# fpga_block.net
KiCad netlist of a schematic drawn in Altium Designer
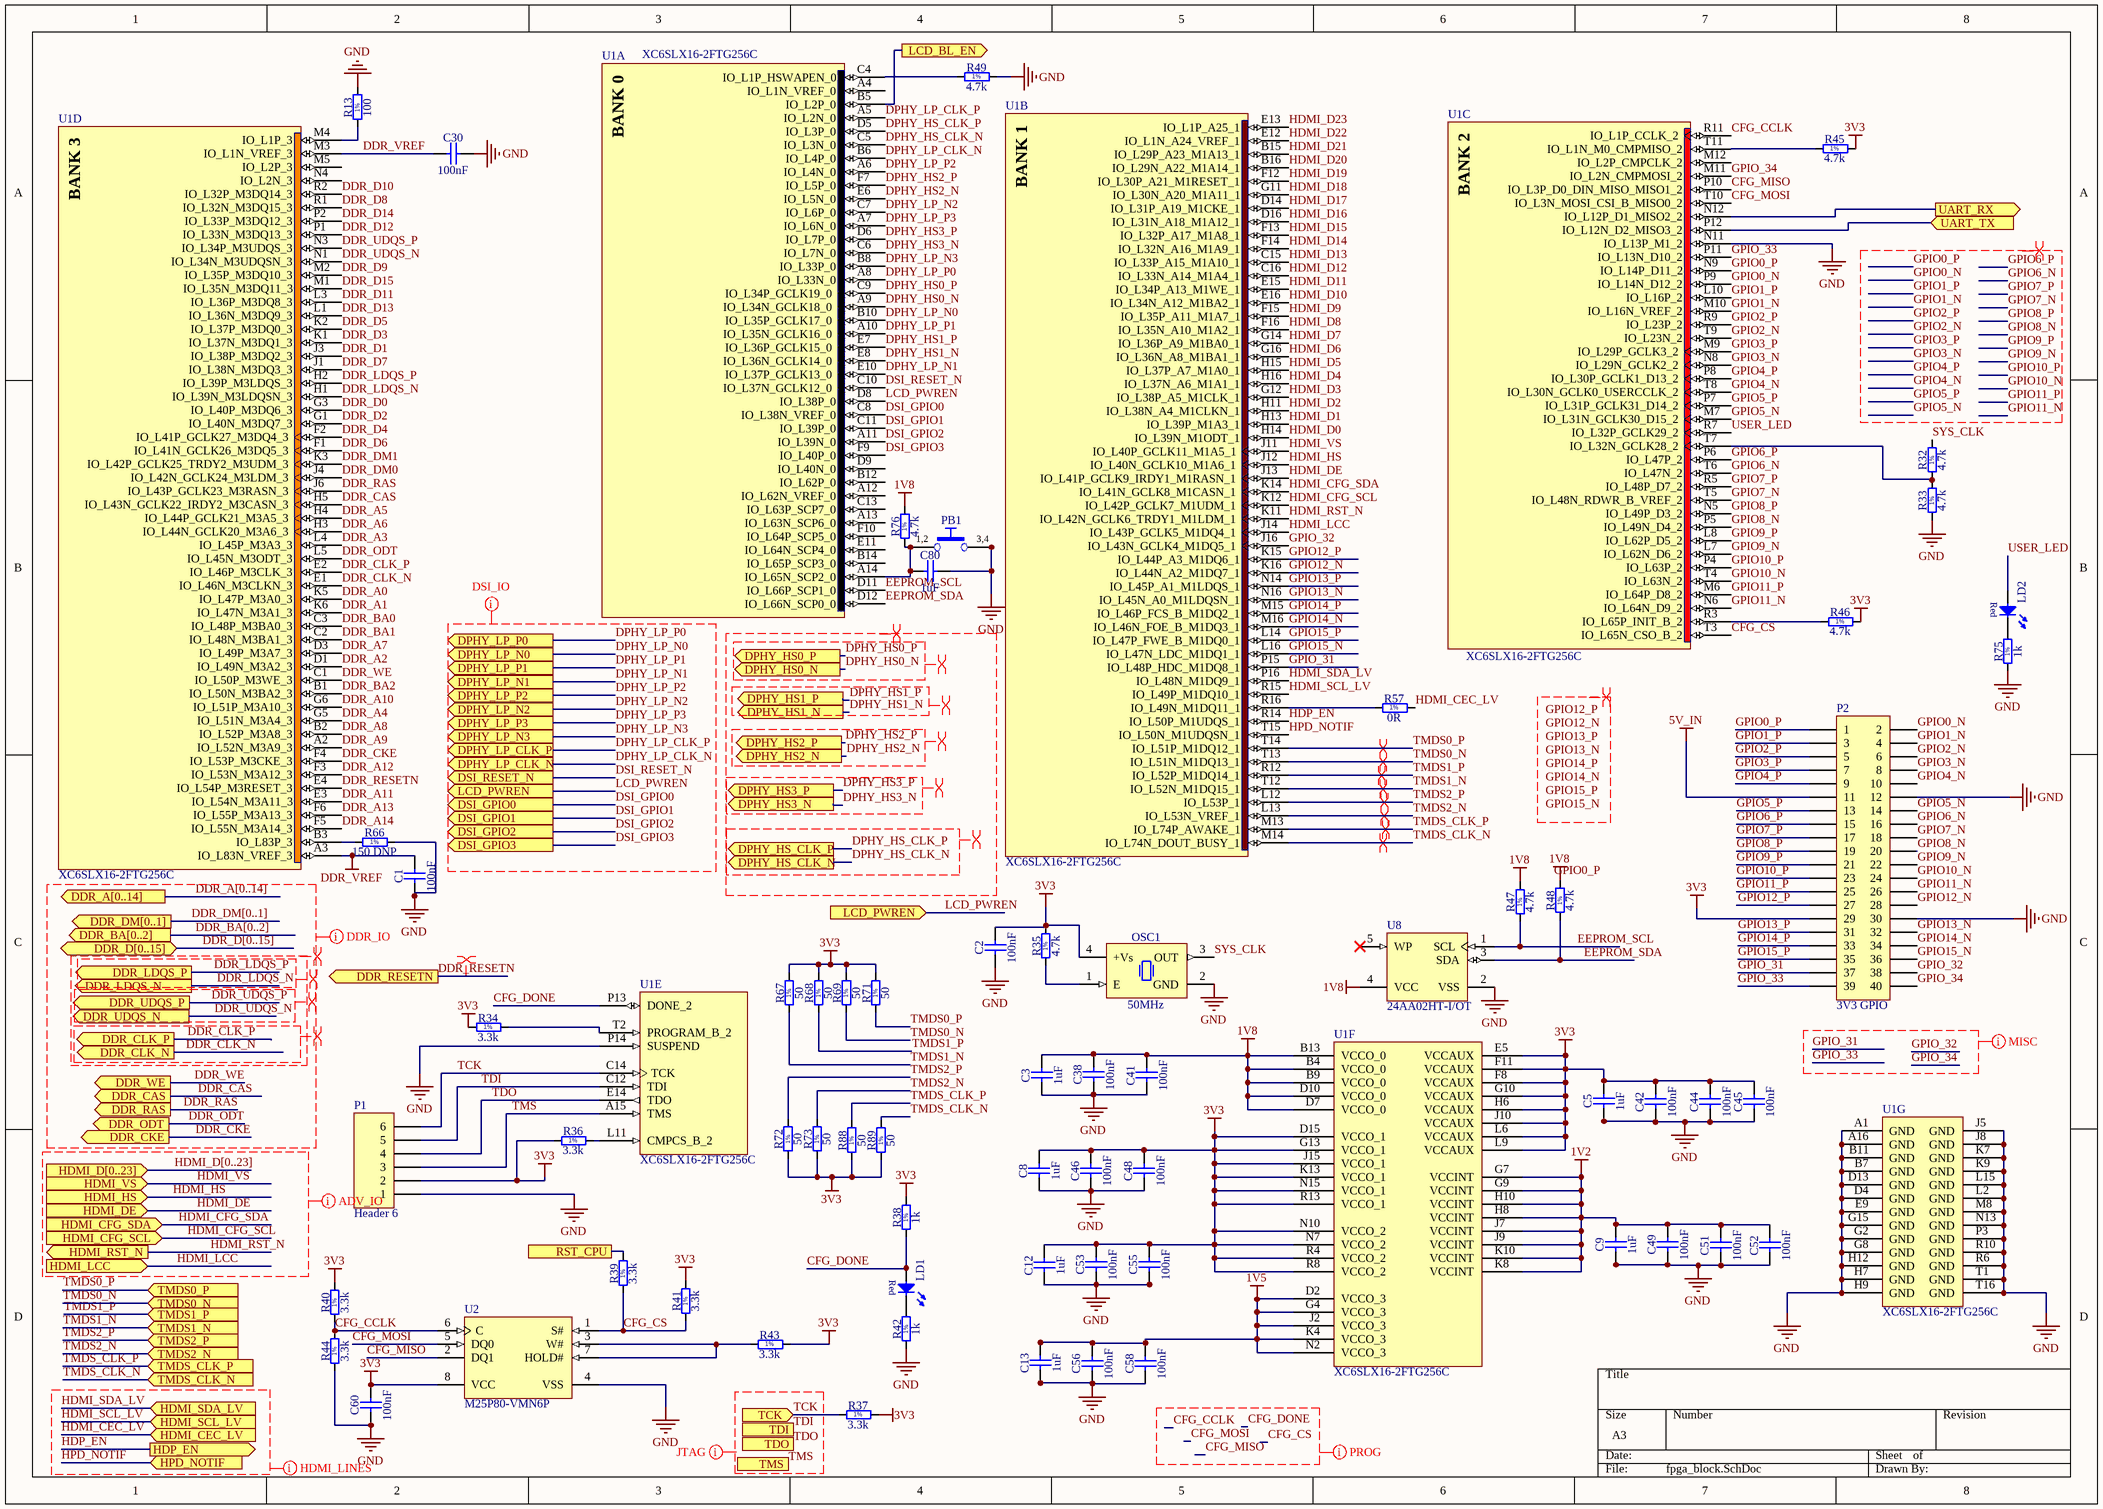
[diagram p0: fpga_block.SchDoc]

(export (version "E")
  (design (tool "Eeschema 10.0.6"))
  (components
    (comp (ref "C1")
      (value "100nF")
      (footprint "CAPC1005X55N")
      (description "Non-polarised capacitor")
      (fields
        (field (name "PART NUMBER") "CC0402_100NF_16V_10%_X5R")
        (field (name "VOLTAGE") "16V")
        (field (name "AUTHOR") "CERN DEM JLC")
      )
      (libsource (lib "Capacitors") (part "Capacitor - non polarized"))
    )
    (comp (ref "C2")
      (value "100nF")
      (footprint "CAPC1005X55N")
      (description "Non-polarised capacitor")
      (fields
        (field (name "PART NUMBER") "CC0402_100NF_16V_10%_X5R")
        (field (name "VOLTAGE") "16V")
        (field (name "AUTHOR") "CERN DEM JLC")
      )
      (libsource (lib "Capacitors") (part "Capacitor - non polarized"))
    )
    (comp (ref "C3")
      (value "1uF")
      (footprint "CAPC1005X55N")
      (description "Non-polarised capacitor")
      (fields
        (field (name "PART NUMBER") "CC0402_100NF_16V_10%_X5R")
        (field (name "VOLTAGE") "16V")
        (field (name "AUTHOR") "CERN DEM JLC")
      )
      (libsource (lib "Capacitors") (part "Capacitor - non polarized"))
    )
    (comp (ref "C5")
      (value "1uF")
      (footprint "CAPC1005X55N")
      (description "Non-polarised capacitor")
      (fields
        (field (name "PART NUMBER") "CC0402_100NF_16V_10%_X5R")
        (field (name "VOLTAGE") "16V")
        (field (name "AUTHOR") "CERN DEM JLC")
      )
      (libsource (lib "Capacitors") (part "Capacitor - non polarized"))
    )
    (comp (ref "C8")
      (value "1uF")
      (footprint "CAPC1005X55N")
      (description "Non-polarised capacitor")
      (fields
        (field (name "PART NUMBER") "CC0402_100NF_16V_10%_X5R")
        (field (name "VOLTAGE") "16V")
        (field (name "AUTHOR") "CERN DEM JLC")
      )
      (libsource (lib "Capacitors") (part "Capacitor - non polarized"))
    )
    (comp (ref "C9")
      (value "1uF")
      (footprint "CAPC1005X55N")
      (description "Non-polarised capacitor")
      (fields
        (field (name "PART NUMBER") "CC0402_100NF_16V_10%_X5R")
        (field (name "VOLTAGE") "16V")
        (field (name "AUTHOR") "CERN DEM JLC")
      )
      (libsource (lib "Capacitors") (part "Capacitor - non polarized"))
    )
    (comp (ref "C12")
      (value "1uF")
      (footprint "CAPC1005X55N")
      (description "Non-polarised capacitor")
      (fields
        (field (name "PART NUMBER") "CC0402_100NF_16V_10%_X5R")
        (field (name "VOLTAGE") "16V")
        (field (name "AUTHOR") "CERN DEM JLC")
      )
      (libsource (lib "Capacitors") (part "Capacitor - non polarized"))
    )
    (comp (ref "C13")
      (value "1uF")
      (footprint "CAPC1005X55N")
      (description "Non-polarised capacitor")
      (fields
        (field (name "PART NUMBER") "CC0402_100NF_16V_10%_X5R")
        (field (name "VOLTAGE") "16V")
        (field (name "AUTHOR") "CERN DEM JLC")
      )
      (libsource (lib "Capacitors") (part "Capacitor - non polarized"))
    )
    (comp (ref "C30")
      (value "100nF")
      (footprint "CAPC1005X55N")
      (description "Non-polarised capacitor")
      (fields
        (field (name "PART NUMBER") "CC0402_100NF_16V_10%_X5R")
        (field (name "VOLTAGE") "16V")
        (field (name "AUTHOR") "CERN DEM JLC")
      )
      (libsource (lib "Capacitors") (part "Capacitor - non polarized"))
    )
    (comp (ref "C38")
      (value "100nF")
      (footprint "CAPC1005X55N")
      (description "Non-polarised capacitor")
      (fields
        (field (name "PART NUMBER") "CC0402_100NF_16V_10%_X5R")
        (field (name "VOLTAGE") "16V")
        (field (name "AUTHOR") "CERN DEM JLC")
      )
      (libsource (lib "Capacitors") (part "Capacitor - non polarized"))
    )
    (comp (ref "C41")
      (value "100nF")
      (footprint "CAPC1005X55N")
      (description "Non-polarised capacitor")
      (fields
        (field (name "PART NUMBER") "CC0402_100NF_16V_10%_X5R")
        (field (name "VOLTAGE") "16V")
        (field (name "AUTHOR") "CERN DEM JLC")
      )
      (libsource (lib "Capacitors") (part "Capacitor - non polarized"))
    )
    (comp (ref "C42")
      (value "100nF")
      (footprint "CAPC1005X55N")
      (description "Non-polarised capacitor")
      (fields
        (field (name "PART NUMBER") "CC0402_100NF_16V_10%_X5R")
        (field (name "VOLTAGE") "16V")
        (field (name "AUTHOR") "CERN DEM JLC")
      )
      (libsource (lib "Capacitors") (part "Capacitor - non polarized"))
    )
    (comp (ref "C44")
      (value "100nF")
      (footprint "CAPC1005X55N")
      (description "Non-polarised capacitor")
      (fields
        (field (name "PART NUMBER") "CC0402_100NF_16V_10%_X5R")
        (field (name "VOLTAGE") "16V")
        (field (name "AUTHOR") "CERN DEM JLC")
      )
      (libsource (lib "Capacitors") (part "Capacitor - non polarized"))
    )
    (comp (ref "C45")
      (value "100nF")
      (footprint "CAPC1005X55N")
      (description "Non-polarised capacitor")
      (fields
        (field (name "PART NUMBER") "CC0402_100NF_16V_10%_X5R")
        (field (name "VOLTAGE") "16V")
        (field (name "AUTHOR") "CERN DEM JLC")
      )
      (libsource (lib "Capacitors") (part "Capacitor - non polarized"))
    )
    (comp (ref "C46")
      (value "100nF")
      (footprint "CAPC1005X55N")
      (description "Non-polarised capacitor")
      (fields
        (field (name "PART NUMBER") "CC0402_100NF_16V_10%_X5R")
        (field (name "VOLTAGE") "16V")
        (field (name "AUTHOR") "CERN DEM JLC")
      )
      (libsource (lib "Capacitors") (part "Capacitor - non polarized"))
    )
    (comp (ref "C48")
      (value "100nF")
      (footprint "CAPC1005X55N")
      (description "Non-polarised capacitor")
      (fields
        (field (name "PART NUMBER") "CC0402_100NF_16V_10%_X5R")
        (field (name "VOLTAGE") "16V")
        (field (name "AUTHOR") "CERN DEM JLC")
      )
      (libsource (lib "Capacitors") (part "Capacitor - non polarized"))
    )
    (comp (ref "C49")
      (value "100nF")
      (footprint "CAPC1005X55N")
      (description "Non-polarised capacitor")
      (fields
        (field (name "PART NUMBER") "CC0402_100NF_16V_10%_X5R")
        (field (name "VOLTAGE") "16V")
        (field (name "AUTHOR") "CERN DEM JLC")
      )
      (libsource (lib "Capacitors") (part "Capacitor - non polarized"))
    )
    (comp (ref "C51")
      (value "100nF")
      (footprint "CAPC1005X55N")
      (description "Non-polarised capacitor")
      (fields
        (field (name "PART NUMBER") "CC0402_100NF_16V_10%_X5R")
        (field (name "VOLTAGE") "16V")
        (field (name "AUTHOR") "CERN DEM JLC")
      )
      (libsource (lib "Capacitors") (part "Capacitor - non polarized"))
    )
    (comp (ref "C52")
      (value "100nF")
      (footprint "CAPC1005X55N")
      (description "Non-polarised capacitor")
      (fields
        (field (name "PART NUMBER") "CC0402_100NF_16V_10%_X5R")
        (field (name "VOLTAGE") "16V")
        (field (name "AUTHOR") "CERN DEM JLC")
      )
      (libsource (lib "Capacitors") (part "Capacitor - non polarized"))
    )
    (comp (ref "C53")
      (value "100nF")
      (footprint "CAPC1005X55N")
      (description "Non-polarised capacitor")
      (fields
        (field (name "PART NUMBER") "CC0402_100NF_16V_10%_X5R")
        (field (name "VOLTAGE") "16V")
        (field (name "AUTHOR") "CERN DEM JLC")
      )
      (libsource (lib "Capacitors") (part "Capacitor - non polarized"))
    )
    (comp (ref "C55")
      (value "100nF")
      (footprint "CAPC1005X55N")
      (description "Non-polarised capacitor")
      (fields
        (field (name "PART NUMBER") "CC0402_100NF_16V_10%_X5R")
        (field (name "VOLTAGE") "16V")
        (field (name "AUTHOR") "CERN DEM JLC")
      )
      (libsource (lib "Capacitors") (part "Capacitor - non polarized"))
    )
    (comp (ref "C56")
      (value "100nF")
      (footprint "CAPC1005X55N")
      (description "Non-polarised capacitor")
      (fields
        (field (name "PART NUMBER") "CC0402_100NF_16V_10%_X5R")
        (field (name "VOLTAGE") "16V")
        (field (name "AUTHOR") "CERN DEM JLC")
      )
      (libsource (lib "Capacitors") (part "Capacitor - non polarized"))
    )
    (comp (ref "C58")
      (value "100nF")
      (footprint "CAPC1005X55N")
      (description "Non-polarised capacitor")
      (fields
        (field (name "PART NUMBER") "CC0402_100NF_16V_10%_X5R")
        (field (name "VOLTAGE") "16V")
        (field (name "AUTHOR") "CERN DEM JLC")
      )
      (libsource (lib "Capacitors") (part "Capacitor - non polarized"))
    )
    (comp (ref "C60")
      (value "100nF")
      (footprint "CAPC2013X100N")
      (description "Non-polarised capacitor")
      (fields
        (field (name "PART NUMBER") "CC0805_1.5NF_50V_5%_C0G")
        (field (name "VOLTAGE") "50V")
        (field (name "AUTHOR") "CERN DEM BC")
      )
      (libsource (lib "Capacitors") (part "Capacitor - non polarized"))
    )
    (comp (ref "C80")
      (value "1uF")
      (footprint "CAPC1005X55N")
      (description "Non-polarised capacitor")
      (fields
        (field (name "PART NUMBER") "CC0402_100NF_16V_10%_X5R")
        (field (name "VOLTAGE") "16V")
        (field (name "AUTHOR") "CERN DEM JLC")
      )
      (libsource (lib "Capacitors") (part "Capacitor - non polarized"))
    )
    (comp (ref "LD1")
      (value "Super Red")
      (footprint "LED_OSRAM_LSR976")
      (description "LED Red 1C 2A")
      (fields
        (field (name "PART NUMBER") "LED_OSRAM_LSR976")
        (field (name "MANUFACTURER") "OSRAM")
        (field (name "AUTHOR") "CERN DEM JLC")
      )
      (libsource (lib "ICs And Semiconductors") (part "LED Red 1C 2A"))
    )
    (comp (ref "LD2")
      (value "Super Red")
      (footprint "LED_OSRAM_LSR976")
      (description "LED Red 1C 2A")
      (fields
        (field (name "PART NUMBER") "LED_OSRAM_LSR976")
        (field (name "MANUFACTURER") "OSRAM")
        (field (name "AUTHOR") "CERN DEM JLC")
      )
      (libsource (lib "ICs And Semiconductors") (part "LED Red 1C 2A"))
    )
    (comp (ref "OSC1")
      (value "50MHz")
      (footprint "OSC_IQD_CFPS-69")
      (description "Oscillator 4 pins 1=E 2=GND 3=OUT 4=+Vs")
      (fields
        (field (name "PART NUMBER") "OSC_50MHZ_IQD_LFSPXO009592")
        (field (name "MANUFACTURER") "IQD FREQUENCY PRODUCTS")
        (field (name "AUTHOR") "CERN DEM JLC")
      )
      (libsource (lib "ICs And Semiconductors") (part "Oscillator 1E 2GND 3OUT 4Vs"))
    )
    (comp (ref "P1")
      (value "Header 6")
      (footprint "HDR1X6")
      (description "Header, 6-Pin")
      (fields (field (name "PUBLISHER") "Altium Limited"))
      (libsource (lib "Miscellaneous Connectors") (part "Header 6"))
    )
    (comp (ref "P2")
      (value "3V3 GPIO")
      (footprint "HDR2X20")
      (description "Header, 20-Pin, Dual row")
      (fields (field (name "PUBLISHER") "Altium Limited"))
      (libsource (lib "Miscellaneous Connectors") (part "Header 20X2"))
    )
    (comp (ref "PB1")
      (value "Push Button")
      (footprint "PB_TYCO_FSM6JSMA")
      (description "Push-Button Switch SPDT")
      (fields
        (field (name "PART NUMBER") "PB_TYCO_FSM6JSMA")
        (field (name "MANUFACTURER") "TYCO ELECTRONICS")
        (field (name "AUTHOR") "CERN DEM JLC")
      )
      (libsource (lib "Eletro-mechanical") (part "PB SPST 12NO-34NO"))
    )
    (comp (ref "R13")
      (value "100")
      (footprint "RESC1608X55N")
      (description "Resistor - 1%")
      (fields
        (field (name "PART NUMBER") "R0603_100K_1%_0.1W_100PPM")
        (field (name "POWER") "0.1W")
        (field (name "AUTHOR") "CERN DEM JLC")
      )
      (libsource (lib "Resistors") (part "Resistor - 1%"))
    )
    (comp (ref "R32")
      (value "4.7k")
      (footprint "RESC1608X55N")
      (description "Resistor - 1%")
      (fields
        (field (name "PART NUMBER") "R0603_100K_1%_0.1W_100PPM")
        (field (name "POWER") "0.1W")
        (field (name "AUTHOR") "CERN DEM JLC")
      )
      (libsource (lib "Resistors") (part "Resistor - 1%"))
    )
    (comp (ref "R33")
      (value "4.7k")
      (footprint "RESC1608X55N")
      (description "Resistor - 1%")
      (fields
        (field (name "PART NUMBER") "R0603_100K_1%_0.1W_100PPM")
        (field (name "POWER") "0.1W")
        (field (name "AUTHOR") "CERN DEM JLC")
      )
      (libsource (lib "Resistors") (part "Resistor - 1%"))
    )
    (comp (ref "R34")
      (value "3.3k")
      (footprint "RESC1608X55N")
      (description "Resistor - 1%")
      (fields
        (field (name "PART NUMBER") "R0603_100K_1%_0.1W_100PPM")
        (field (name "POWER") "0.1W")
        (field (name "AUTHOR") "CERN DEM JLC")
      )
      (libsource (lib "Resistors") (part "Resistor - 1%"))
    )
    (comp (ref "R35")
      (value "4.7k")
      (footprint "RESC1608X55N")
      (description "Resistor - 1%")
      (fields
        (field (name "PART NUMBER") "R0603_100K_1%_0.1W_100PPM")
        (field (name "POWER") "0.1W")
        (field (name "AUTHOR") "CERN DEM JLC")
      )
      (libsource (lib "Resistors") (part "Resistor - 1%"))
    )
    (comp (ref "R36")
      (value "3.3k")
      (footprint "RESC1608X55N")
      (description "Resistor - 1%")
      (fields
        (field (name "PART NUMBER") "R0603_100K_1%_0.1W_100PPM")
        (field (name "POWER") "0.1W")
        (field (name "AUTHOR") "CERN DEM JLC")
      )
      (libsource (lib "Resistors") (part "Resistor - 1%"))
    )
    (comp (ref "R37")
      (value "3.3k")
      (footprint "RESC1608X55N")
      (description "Resistor - 1%")
      (fields
        (field (name "PART NUMBER") "R0603_100K_1%_0.1W_100PPM")
        (field (name "POWER") "0.1W")
        (field (name "AUTHOR") "CERN DEM JLC")
      )
      (libsource (lib "Resistors") (part "Resistor - 1%"))
    )
    (comp (ref "R38")
      (value "1k")
      (footprint "RESC1608X55N")
      (description "Resistor - 1%")
      (fields
        (field (name "PART NUMBER") "R0603_100K_1%_0.1W_100PPM")
        (field (name "POWER") "0.1W")
        (field (name "AUTHOR") "CERN DEM JLC")
      )
      (libsource (lib "Resistors") (part "Resistor - 1%"))
    )
    (comp (ref "R39")
      (value "3.3k")
      (footprint "RESC1608X55N")
      (description "Resistor - 1%")
      (fields
        (field (name "PART NUMBER") "R0603_100K_1%_0.1W_100PPM")
        (field (name "POWER") "0.1W")
        (field (name "AUTHOR") "CERN DEM JLC")
      )
      (libsource (lib "Resistors") (part "Resistor - 1%"))
    )
    (comp (ref "R40")
      (value "3.3k")
      (footprint "RESC1608X55N")
      (description "Resistor - 1%")
      (fields
        (field (name "PART NUMBER") "R0603_100K_1%_0.1W_100PPM")
        (field (name "POWER") "0.1W")
        (field (name "AUTHOR") "CERN DEM JLC")
      )
      (libsource (lib "Resistors") (part "Resistor - 1%"))
    )
    (comp (ref "R41")
      (value "3.3k")
      (footprint "RESC1608X55N")
      (description "Resistor - 1%")
      (fields
        (field (name "PART NUMBER") "R0603_100K_1%_0.1W_100PPM")
        (field (name "POWER") "0.1W")
        (field (name "AUTHOR") "CERN DEM JLC")
      )
      (libsource (lib "Resistors") (part "Resistor - 1%"))
    )
    (comp (ref "R42")
      (value "1k")
      (footprint "RESC1608X55N")
      (description "Resistor - 1%")
      (fields
        (field (name "PART NUMBER") "R0603_100K_1%_0.1W_100PPM")
        (field (name "POWER") "0.1W")
        (field (name "AUTHOR") "CERN DEM JLC")
      )
      (libsource (lib "Resistors") (part "Resistor - 1%"))
    )
    (comp (ref "R43")
      (value "3.3k")
      (footprint "RESC1608X55N")
      (description "Resistor - 1%")
      (fields
        (field (name "PART NUMBER") "R0603_100K_1%_0.1W_100PPM")
        (field (name "POWER") "0.1W")
        (field (name "AUTHOR") "CERN DEM JLC")
      )
      (libsource (lib "Resistors") (part "Resistor - 1%"))
    )
    (comp (ref "R44")
      (value "3.3k")
      (footprint "RESC1608X55N")
      (description "Resistor - 1%")
      (fields
        (field (name "PART NUMBER") "R0603_100K_1%_0.1W_100PPM")
        (field (name "POWER") "0.1W")
        (field (name "AUTHOR") "CERN DEM JLC")
      )
      (libsource (lib "Resistors") (part "Resistor - 1%"))
    )
    (comp (ref "R45")
      (value "4.7k")
      (footprint "RESC1608X55N")
      (description "Resistor - 1%")
      (fields
        (field (name "PART NUMBER") "R0603_100K_1%_0.1W_100PPM")
        (field (name "POWER") "0.1W")
        (field (name "AUTHOR") "CERN DEM JLC")
      )
      (libsource (lib "Resistors") (part "Resistor - 1%"))
    )
    (comp (ref "R46")
      (value "4.7k")
      (footprint "RESC1608X55N")
      (description "Resistor - 1%")
      (fields
        (field (name "PART NUMBER") "R0603_100K_1%_0.1W_100PPM")
        (field (name "POWER") "0.1W")
        (field (name "AUTHOR") "CERN DEM JLC")
      )
      (libsource (lib "Resistors") (part "Resistor - 1%"))
    )
    (comp (ref "R47")
      (value "4.7k")
      (footprint "RESC1608X55N")
      (description "Resistor - 1%")
      (fields
        (field (name "PART NUMBER") "R0603_100K_1%_0.1W_100PPM")
        (field (name "POWER") "0.1W")
        (field (name "AUTHOR") "CERN DEM JLC")
      )
      (libsource (lib "Resistors") (part "Resistor - 1%"))
    )
    (comp (ref "R48")
      (value "4.7k")
      (footprint "RESC1608X55N")
      (description "Resistor - 1%")
      (fields
        (field (name "PART NUMBER") "R0603_100K_1%_0.1W_100PPM")
        (field (name "POWER") "0.1W")
        (field (name "AUTHOR") "CERN DEM JLC")
      )
      (libsource (lib "Resistors") (part "Resistor - 1%"))
    )
    (comp (ref "R49")
      (value "4.7k")
      (footprint "RESC1608X55N")
      (description "Resistor - 1%")
      (fields
        (field (name "PART NUMBER") "R0603_100K_1%_0.1W_100PPM")
        (field (name "POWER") "0.1W")
        (field (name "AUTHOR") "CERN DEM JLC")
      )
      (libsource (lib "Resistors") (part "Resistor - 1%"))
    )
    (comp (ref "R57")
      (value "0R")
      (footprint "RESC1608X55N")
      (description "Resistor - 1%")
      (fields
        (field (name "PART NUMBER") "R0603_100K_1%_0.1W_100PPM")
        (field (name "POWER") "0.1W")
        (field (name "AUTHOR") "CERN DEM JLC")
      )
      (libsource (lib "Resistors") (part "Resistor - 1%"))
    )
    (comp (ref "R66")
      (value "150 DNP")
      (footprint "RESC1608X55N")
      (description "Resistor - 1%")
      (fields
        (field (name "PART NUMBER") "R0603_100K_1%_0.1W_100PPM")
        (field (name "POWER") "0.1W")
        (field (name "AUTHOR") "CERN DEM JLC")
      )
      (libsource (lib "Resistors") (part "Resistor - 1%"))
    )
    (comp (ref "R67")
      (value "50")
      (footprint "RESC1005X40N")
      (description "Resistor - 1%")
      (fields
        (field (name "PART NUMBER") "R0402_51K_1%_0.0625W_100PPM")
        (field (name "POWER") "0.0625W")
        (field (name "AUTHOR") "CERN DEM JLC")
      )
      (libsource (lib "Resistors") (part "Resistor - 1%"))
    )
    (comp (ref "R68")
      (value "50")
      (footprint "RESC1005X40N")
      (description "Resistor - 1%")
      (fields
        (field (name "PART NUMBER") "R0402_51K_1%_0.0625W_100PPM")
        (field (name "POWER") "0.0625W")
        (field (name "AUTHOR") "CERN DEM JLC")
      )
      (libsource (lib "Resistors") (part "Resistor - 1%"))
    )
    (comp (ref "R69")
      (value "50")
      (footprint "RESC1005X40N")
      (description "Resistor - 1%")
      (fields
        (field (name "PART NUMBER") "R0402_51K_1%_0.0625W_100PPM")
        (field (name "POWER") "0.0625W")
        (field (name "AUTHOR") "CERN DEM JLC")
      )
      (libsource (lib "Resistors") (part "Resistor - 1%"))
    )
    (comp (ref "R71")
      (value "50")
      (footprint "RESC1005X40N")
      (description "Resistor - 1%")
      (fields
        (field (name "PART NUMBER") "R0402_51K_1%_0.0625W_100PPM")
        (field (name "POWER") "0.0625W")
        (field (name "AUTHOR") "CERN DEM JLC")
      )
      (libsource (lib "Resistors") (part "Resistor - 1%"))
    )
    (comp (ref "R72")
      (value "50")
      (footprint "RESC1005X40N")
      (description "Resistor - 1%")
      (fields
        (field (name "PART NUMBER") "R0402_51K_1%_0.0625W_100PPM")
        (field (name "POWER") "0.0625W")
        (field (name "AUTHOR") "CERN DEM JLC")
      )
      (libsource (lib "Resistors") (part "Resistor - 1%"))
    )
    (comp (ref "R73")
      (value "50")
      (footprint "RESC1005X40N")
      (description "Resistor - 1%")
      (fields
        (field (name "PART NUMBER") "R0402_51K_1%_0.0625W_100PPM")
        (field (name "POWER") "0.0625W")
        (field (name "AUTHOR") "CERN DEM JLC")
      )
      (libsource (lib "Resistors") (part "Resistor - 1%"))
    )
    (comp (ref "R75")
      (value "1k")
      (footprint "RESC1608X55N")
      (description "Resistor - 1%")
      (fields
        (field (name "PART NUMBER") "R0603_100K_1%_0.1W_100PPM")
        (field (name "POWER") "0.1W")
        (field (name "AUTHOR") "CERN DEM JLC")
      )
      (libsource (lib "Resistors") (part "Resistor - 1%"))
    )
    (comp (ref "R76")
      (value "4.7k")
      (footprint "RESC1608X55N")
      (description "Resistor - 1%")
      (fields
        (field (name "PART NUMBER") "R0603_100K_1%_0.1W_100PPM")
        (field (name "POWER") "0.1W")
        (field (name "AUTHOR") "CERN DEM JLC")
      )
      (libsource (lib "Resistors") (part "Resistor - 1%"))
    )
    (comp (ref "R88")
      (value "50")
      (footprint "RESC1005X40N")
      (description "Resistor - 1%")
      (fields
        (field (name "PART NUMBER") "R0402_51K_1%_0.0625W_100PPM")
        (field (name "POWER") "0.0625W")
        (field (name "AUTHOR") "CERN DEM JLC")
      )
      (libsource (lib "Resistors") (part "Resistor - 1%"))
    )
    (comp (ref "R89")
      (value "50")
      (footprint "RESC1005X40N")
      (description "Resistor - 1%")
      (fields
        (field (name "PART NUMBER") "R0402_51K_1%_0.0625W_100PPM")
        (field (name "POWER") "0.0625W")
        (field (name "AUTHOR") "CERN DEM JLC")
      )
      (libsource (lib "Resistors") (part "Resistor - 1%"))
    )
    (comp (ref "U1")
      (value "XC6SLX16-2FTG256C")
      (footprint "FTG256")
      (libsource (lib "Xilinx Spartan-6") (part "XC6SLX16-2FTG256C"))
    )
    (comp (ref "U2")
      (value "M25P80-VMN6P")
      (footprint "MICT-MN-8_N")
      (description "8 Mb (x1) Serial NOR Flash Memory, 75 MHz, 2.7 to 3.6 V, 8-pin SO8 Narrow (MN), Tube")
      (fields (field (name "VOLTAGE") "2.7V-3.6V") (field (name "MANUFACTURER") "Micron"))
      (libsource (lib "Micron Memory Serial NOR Flash") (part "M25P80-VMN6P"))
    )
    (comp (ref "U8")
      (value "24AA02HT-I/OT")
      (footprint "SOT-23-OT5_L")
      (description "2Kbit, 400kHz, 1.7V, I2C Serial EEPROM, 5-Pin SOT-23, Industrial Temperature, Tape and Reel")
      (fields (field (name "MANUFACTURER") "Microchip"))
      (libsource (lib "Microchip I2C Serial EEPROM") (part "24AA02HT-I/OT"))
    )
  )
  (nets
    (net (code "1") (name "/CFG_CCLK") (class "Default")
      (node (ref "R40") (pin "1") (pinfunction "1_1") (pintype "passive"))
      (node (ref "R44") (pin "2") (pinfunction "2_2") (pintype "passive"))
      (node (ref "U1") (pin "R11") (pinfunction "IO_L1P_CCLK_2_R11") (pintype "bidirectional"))
      (node (ref "U2") (pin "6") (pinfunction "C_6") (pintype "input"))
    )
    (net (code "2") (name "/CFG_CS") (class "Default")
      (node (ref "R39") (pin "1") (pinfunction "1_1") (pintype "passive"))
      (node (ref "R41") (pin "1") (pinfunction "1_1") (pintype "passive"))
      (node (ref "U1") (pin "T3") (pinfunction "IO_L65N_CSO_B_2_T3") (pintype "bidirectional"))
      (node (ref "U2") (pin "1") (pinfunction "S#_1") (pintype "input"))
    )
    (net (code "3") (name "/CFG_DONE") (class "Default")
      (node (ref "LD1") (pin "2") (pinfunction "A_2") (pintype "passive"))
      (node (ref "R38") (pin "1") (pinfunction "1_1") (pintype "passive"))
      (node (ref "U1") (pin "P13") (pinfunction "DONE_2_P13") (pintype "bidirectional"))
    )
    (net (code "4") (name "/CFG_MISO") (class "Default")
      (node (ref "U1") (pin "P10") (pinfunction "IO_L3P_D0_DIN_MISO_MISO1_2_P10") (pintype "bidirectional"))
      (node (ref "U2") (pin "2") (pinfunction "DQ1_2") (pintype "tri_state"))
    )
    (net (code "5") (name "/CFG_MOSI") (class "Default")
      (node (ref "U1") (pin "T10") (pinfunction "IO_L3N_MOSI_CSI_B_MISO0_2_T10") (pintype "bidirectional"))
      (node (ref "U2") (pin "5") (pinfunction "DQ0_5") (pintype "input"))
    )
    (net (code "6") (name "/DDR_A0") (class "Default")
      (node (ref "U1") (pin "K5") (pinfunction "IO_L47P_M3A0_3_K5") (pintype "bidirectional"))
    )
    (net (code "7") (name "/DDR_A1") (class "Default")
      (node (ref "U1") (pin "K6") (pinfunction "IO_L47N_M3A1_3_K6") (pintype "bidirectional"))
    )
    (net (code "8") (name "/DDR_A2") (class "Default")
      (node (ref "U1") (pin "D1") (pinfunction "IO_L49N_M3A2_3_D1") (pintype "bidirectional"))
    )
    (net (code "9") (name "/DDR_A3") (class "Default")
      (node (ref "U1") (pin "L4") (pinfunction "IO_L45P_M3A3_3_L4") (pintype "bidirectional"))
    )
    (net (code "10") (name "/DDR_A4") (class "Default")
      (node (ref "U1") (pin "G5") (pinfunction "IO_L51N_M3A4_3_G5") (pintype "bidirectional"))
    )
    (net (code "11") (name "/DDR_A5") (class "Default")
      (node (ref "U1") (pin "H4") (pinfunction "IO_L44P_GCLK21_M3A5_3_H4") (pintype "bidirectional"))
    )
    (net (code "12") (name "/DDR_A6") (class "Default")
      (node (ref "U1") (pin "H3") (pinfunction "IO_L44N_GCLK20_M3A6_3_H3") (pintype "bidirectional"))
    )
    (net (code "13") (name "/DDR_A7") (class "Default")
      (node (ref "U1") (pin "D3") (pinfunction "IO_L49P_M3A7_3_D3") (pintype "bidirectional"))
    )
    (net (code "14") (name "/DDR_A8") (class "Default")
      (node (ref "U1") (pin "B2") (pinfunction "IO_L52P_M3A8_3_B2") (pintype "bidirectional"))
    )
    (net (code "15") (name "/DDR_A9") (class "Default")
      (node (ref "U1") (pin "A2") (pinfunction "IO_L52N_M3A9_3_A2") (pintype "bidirectional"))
    )
    (net (code "16") (name "/DDR_A10") (class "Default")
      (node (ref "U1") (pin "G6") (pinfunction "IO_L51P_M3A10_3_G6") (pintype "bidirectional"))
    )
    (net (code "17") (name "/DDR_A11") (class "Default")
      (node (ref "U1") (pin "E3") (pinfunction "IO_L54N_M3A11_3_E3") (pintype "bidirectional"))
    )
    (net (code "18") (name "/DDR_A12") (class "Default")
      (node (ref "U1") (pin "F3") (pinfunction "IO_L53N_M3A12_3_F3") (pintype "bidirectional"))
    )
    (net (code "19") (name "/DDR_A13") (class "Default")
      (node (ref "U1") (pin "F6") (pinfunction "IO_L55P_M3A13_3_F6") (pintype "bidirectional"))
    )
    (net (code "20") (name "/DDR_A14") (class "Default")
      (node (ref "U1") (pin "F5") (pinfunction "IO_L55N_M3A14_3_F5") (pintype "bidirectional"))
    )
    (net (code "22") (name "/DDR_BA0") (class "Default")
      (node (ref "U1") (pin "C3") (pinfunction "IO_L48P_M3BA0_3_C3") (pintype "bidirectional"))
    )
    (net (code "23") (name "/DDR_BA1") (class "Default")
      (node (ref "U1") (pin "C2") (pinfunction "IO_L48N_M3BA1_3_C2") (pintype "bidirectional"))
    )
    (net (code "24") (name "/DDR_BA2") (class "Default")
      (node (ref "U1") (pin "B1") (pinfunction "IO_L50N_M3BA2_3_B1") (pintype "bidirectional"))
    )
    (net (code "26") (name "/DDR_CAS") (class "Default")
      (node (ref "U1") (pin "H5") (pinfunction "IO_L43N_GCLK22_IRDY2_M3CASN_3_H5") (pintype "bidirectional"))
    )
    (net (code "27") (name "/DDR_CKE") (class "Default")
      (node (ref "U1") (pin "F4") (pinfunction "IO_L53P_M3CKE_3_F4") (pintype "bidirectional"))
    )
    (net (code "28") (name "/DDR_CLK_N") (class "Default")
      (node (ref "U1") (pin "E1") (pinfunction "IO_L46N_M3CLKN_3_E1") (pintype "bidirectional"))
    )
    (net (code "29") (name "/DDR_CLK_P") (class "Default")
      (node (ref "U1") (pin "E2") (pinfunction "IO_L46P_M3CLK_3_E2") (pintype "bidirectional"))
    )
    (net (code "30") (name "/DDR_D0") (class "Default")
      (node (ref "U1") (pin "G3") (pinfunction "IO_L40P_M3DQ6_3_G3") (pintype "bidirectional"))
    )
    (net (code "31") (name "/DDR_D1") (class "Default")
      (node (ref "U1") (pin "J3") (pinfunction "IO_L38P_M3DQ2_3_J3") (pintype "bidirectional"))
    )
    (net (code "32") (name "/DDR_D2") (class "Default")
      (node (ref "U1") (pin "G1") (pinfunction "IO_L40N_M3DQ7_3_G1") (pintype "bidirectional"))
    )
    (net (code "33") (name "/DDR_D3") (class "Default")
      (node (ref "U1") (pin "K1") (pinfunction "IO_L37N_M3DQ1_3_K1") (pintype "bidirectional"))
    )
    (net (code "34") (name "/DDR_D4") (class "Default")
      (node (ref "U1") (pin "F2") (pinfunction "IO_L41P_GCLK27_M3DQ4_3_F2") (pintype "bidirectional"))
    )
    (net (code "35") (name "/DDR_D5") (class "Default")
      (node (ref "U1") (pin "K2") (pinfunction "IO_L37P_M3DQ0_3_K2") (pintype "bidirectional"))
    )
    (net (code "36") (name "/DDR_D6") (class "Default")
      (node (ref "U1") (pin "F1") (pinfunction "IO_L41N_GCLK26_M3DQ5_3_F1") (pintype "bidirectional"))
    )
    (net (code "37") (name "/DDR_D7") (class "Default")
      (node (ref "U1") (pin "J1") (pinfunction "IO_L38N_M3DQ3_3_J1") (pintype "bidirectional"))
    )
    (net (code "38") (name "/DDR_D8") (class "Default")
      (node (ref "U1") (pin "R1") (pinfunction "IO_L32N_M3DQ15_3_R1") (pintype "bidirectional"))
    )
    (net (code "39") (name "/DDR_D9") (class "Default")
      (node (ref "U1") (pin "M2") (pinfunction "IO_L35P_M3DQ10_3_M2") (pintype "bidirectional"))
    )
    (net (code "40") (name "/DDR_D10") (class "Default")
      (node (ref "U1") (pin "R2") (pinfunction "IO_L32P_M3DQ14_3_R2") (pintype "bidirectional"))
    )
    (net (code "41") (name "/DDR_D11") (class "Default")
      (node (ref "U1") (pin "L3") (pinfunction "IO_L36P_M3DQ8_3_L3") (pintype "bidirectional"))
    )
    (net (code "42") (name "/DDR_D12") (class "Default")
      (node (ref "U1") (pin "P1") (pinfunction "IO_L33N_M3DQ13_3_P1") (pintype "bidirectional"))
    )
    (net (code "43") (name "/DDR_D13") (class "Default")
      (node (ref "U1") (pin "L1") (pinfunction "IO_L36N_M3DQ9_3_L1") (pintype "bidirectional"))
    )
    (net (code "44") (name "/DDR_D14") (class "Default")
      (node (ref "U1") (pin "P2") (pinfunction "IO_L33P_M3DQ12_3_P2") (pintype "bidirectional"))
    )
    (net (code "45") (name "/DDR_D15") (class "Default")
      (node (ref "U1") (pin "M1") (pinfunction "IO_L35N_M3DQ11_3_M1") (pintype "bidirectional"))
    )
    (net (code "46") (name "/DDR_DM0") (class "Default")
      (node (ref "U1") (pin "J4") (pinfunction "IO_L42N_GCLK24_M3LDM_3_J4") (pintype "bidirectional"))
    )
    (net (code "47") (name "/DDR_DM1") (class "Default")
      (node (ref "U1") (pin "K3") (pinfunction "IO_L42P_GCLK25_TRDY2_M3UDM_3_K3") (pintype "bidirectional"))
    )
    (net (code "50") (name "/DDR_LDQS_N") (class "Default")
      (node (ref "U1") (pin "H1") (pinfunction "IO_L39N_M3LDQSN_3_H1") (pintype "bidirectional"))
    )
    (net (code "51") (name "/DDR_LDQS_P") (class "Default")
      (node (ref "U1") (pin "H2") (pinfunction "IO_L39P_M3LDQS_3_H2") (pintype "bidirectional"))
    )
    (net (code "52") (name "/DDR_ODT") (class "Default")
      (node (ref "U1") (pin "L5") (pinfunction "IO_L45N_M3ODT_3_L5") (pintype "bidirectional"))
    )
    (net (code "53") (name "/DDR_RAS") (class "Default")
      (node (ref "U1") (pin "J6") (pinfunction "IO_L43P_GCLK23_M3RASN_3_J6") (pintype "bidirectional"))
    )
    (net (code "54") (name "/DDR_RESETN") (class "Default")
      (node (ref "U1") (pin "E4") (pinfunction "IO_L54P_M3RESET_3_E4") (pintype "bidirectional"))
    )
    (net (code "55") (name "/DDR_UDQS_N") (class "Default")
      (node (ref "U1") (pin "N1") (pinfunction "IO_L34N_M3UDQSN_3_N1") (pintype "bidirectional"))
    )
    (net (code "56") (name "/DDR_UDQS_P") (class "Default")
      (node (ref "U1") (pin "N3") (pinfunction "IO_L34P_M3UDQS_3_N3") (pintype "bidirectional"))
    )
    (net (code "57") (name "/DDR_WE") (class "Default")
      (node (ref "U1") (pin "C1") (pinfunction "IO_L50P_M3WE_3_C1") (pintype "bidirectional"))
    )
    (net (code "58") (name "/DPHY_HS0_N") (class "Default")
      (node (ref "U1") (pin "A9") (pinfunction "IO_L34N_GCLK18_0_A9") (pintype "bidirectional"))
    )
    (net (code "59") (name "/DPHY_HS0_P") (class "Default")
      (node (ref "U1") (pin "C9") (pinfunction "IO_L34P_GCLK19_0_C9") (pintype "bidirectional"))
    )
    (net (code "60") (name "/DPHY_HS1_N") (class "Default")
      (node (ref "U1") (pin "E8") (pinfunction "IO_L36N_GCLK14_0_E8") (pintype "bidirectional"))
    )
    (net (code "61") (name "/DPHY_HS1_P") (class "Default")
      (node (ref "U1") (pin "E7") (pinfunction "IO_L36P_GCLK15_0_E7") (pintype "bidirectional"))
    )
    (net (code "62") (name "/DPHY_HS2_N") (class "Default")
      (node (ref "U1") (pin "E6") (pinfunction "IO_L5N_0_E6") (pintype "bidirectional"))
    )
    (net (code "63") (name "/DPHY_HS2_P") (class "Default")
      (node (ref "U1") (pin "F7") (pinfunction "IO_L5P_0_F7") (pintype "bidirectional"))
    )
    (net (code "64") (name "/DPHY_HS3_N") (class "Default")
      (node (ref "U1") (pin "C6") (pinfunction "IO_L7N_0_C6") (pintype "bidirectional"))
    )
    (net (code "65") (name "/DPHY_HS3_P") (class "Default")
      (node (ref "U1") (pin "D6") (pinfunction "IO_L7P_0_D6") (pintype "bidirectional"))
    )
    (net (code "66") (name "/DPHY_HS_CLK_N") (class "Default")
      (node (ref "U1") (pin "C5") (pinfunction "IO_L3N_0_C5") (pintype "bidirectional"))
    )
    (net (code "67") (name "/DPHY_HS_CLK_P") (class "Default")
      (node (ref "U1") (pin "D5") (pinfunction "IO_L3P_0_D5") (pintype "bidirectional"))
    )
    (net (code "68") (name "/DPHY_LP_CLK_N") (class "Default")
      (node (ref "U1") (pin "B6") (pinfunction "IO_L4P_0_B6") (pintype "bidirectional"))
    )
    (net (code "69") (name "/DPHY_LP_CLK_P") (class "Default")
      (node (ref "U1") (pin "A5") (pinfunction "IO_L2N_0_A5") (pintype "bidirectional"))
    )
    (net (code "70") (name "/DPHY_LP_N0") (class "Default")
      (node (ref "U1") (pin "B10") (pinfunction "IO_L35P_GCLK17_0_B10") (pintype "bidirectional"))
    )
    (net (code "71") (name "/DPHY_LP_N1") (class "Default")
      (node (ref "U1") (pin "E10") (pinfunction "IO_L37P_GCLK13_0_E10") (pintype "bidirectional"))
    )
    (net (code "72") (name "/DPHY_LP_N2") (class "Default")
      (node (ref "U1") (pin "C7") (pinfunction "IO_L6P_0_C7") (pintype "bidirectional"))
    )
    (net (code "73") (name "/DPHY_LP_N3") (class "Default")
      (node (ref "U1") (pin "B8") (pinfunction "IO_L33P_0_B8") (pintype "bidirectional"))
    )
    (net (code "74") (name "/DPHY_LP_P0") (class "Default")
      (node (ref "U1") (pin "A8") (pinfunction "IO_L33N_0_A8") (pintype "bidirectional"))
    )
    (net (code "75") (name "/DPHY_LP_P1") (class "Default")
      (node (ref "U1") (pin "A10") (pinfunction "IO_L35N_GCLK16_0_A10") (pintype "bidirectional"))
    )
    (net (code "76") (name "/DPHY_LP_P2") (class "Default")
      (node (ref "U1") (pin "A6") (pinfunction "IO_L4N_0_A6") (pintype "bidirectional"))
    )
    (net (code "77") (name "/DPHY_LP_P3") (class "Default")
      (node (ref "U1") (pin "A7") (pinfunction "IO_L6N_0_A7") (pintype "bidirectional"))
    )
    (net (code "78") (name "/DSI_GPIO0") (class "Default")
      (node (ref "U1") (pin "C8") (pinfunction "IO_L38N_VREF_0_C8") (pintype "bidirectional"))
    )
    (net (code "79") (name "/DSI_GPIO1") (class "Default")
      (node (ref "U1") (pin "C11") (pinfunction "IO_L39P_0_C11") (pintype "bidirectional"))
    )
    (net (code "80") (name "/DSI_GPIO2") (class "Default")
      (node (ref "U1") (pin "A11") (pinfunction "IO_L39N_0_A11") (pintype "bidirectional"))
    )
    (net (code "81") (name "/DSI_GPIO3") (class "Default")
      (node (ref "U1") (pin "F9") (pinfunction "IO_L40P_0_F9") (pintype "bidirectional"))
    )
    (net (code "82") (name "/DSI_RESET_N") (class "Default")
      (node (ref "U1") (pin "C10") (pinfunction "IO_L37N_GCLK12_0_C10") (pintype "bidirectional"))
    )
    (net (code "83") (name "/EEPROM_SCL") (class "Default")
      (node (ref "R47") (pin "1") (pinfunction "1_1") (pintype "passive"))
      (node (ref "U1") (pin "D11") (pinfunction "IO_L66P_SCP1_0_D11") (pintype "bidirectional"))
      (node (ref "U8") (pin "1") (pinfunction "SCL_1") (pintype "input"))
    )
    (net (code "84") (name "/EEPROM_SDA") (class "Default")
      (node (ref "R48") (pin "1") (pinfunction "1_1") (pintype "passive"))
      (node (ref "U1") (pin "D12") (pinfunction "IO_L66N_SCP0_0_D12") (pintype "bidirectional"))
      (node (ref "U8") (pin "3") (pinfunction "SDA_3") (pintype "bidirectional"))
    )
    (net (code "85") (name "/GPIO0_N") (class "Default")
      (node (ref "P2") (pin "2") (pinfunction "2_2") (pintype "passive"))
      (node (ref "U1") (pin "P9") (pinfunction "IO_L14N_D12_2_P9") (pintype "bidirectional"))
    )
    (net (code "86") (name "/GPIO0_P") (class "Default")
      (node (ref "P2") (pin "1") (pinfunction "1_1") (pintype "passive"))
      (node (ref "U1") (pin "N9") (pinfunction "IO_L14P_D11_2_N9") (pintype "bidirectional"))
    )
    (net (code "87") (name "/GPIO1_N") (class "Default")
      (node (ref "P2") (pin "4") (pinfunction "4_4") (pintype "passive"))
      (node (ref "U1") (pin "M10") (pinfunction "IO_L16N_VREF_2_M10") (pintype "bidirectional"))
    )
    (net (code "88") (name "/GPIO1_P") (class "Default")
      (node (ref "P2") (pin "3") (pinfunction "3_3") (pintype "passive"))
      (node (ref "U1") (pin "L10") (pinfunction "IO_L16P_2_L10") (pintype "bidirectional"))
    )
    (net (code "89") (name "/GPIO2_N") (class "Default")
      (node (ref "P2") (pin "6") (pinfunction "6_6") (pintype "passive"))
      (node (ref "U1") (pin "T9") (pinfunction "IO_L23N_2_T9") (pintype "bidirectional"))
    )
    (net (code "90") (name "/GPIO2_P") (class "Default")
      (node (ref "P2") (pin "5") (pinfunction "5_5") (pintype "passive"))
      (node (ref "U1") (pin "R9") (pinfunction "IO_L23P_2_R9") (pintype "bidirectional"))
    )
    (net (code "91") (name "/GPIO3_N") (class "Default")
      (node (ref "P2") (pin "8") (pinfunction "8_8") (pintype "passive"))
      (node (ref "U1") (pin "N8") (pinfunction "IO_L29N_GCLK2_2_N8") (pintype "bidirectional"))
    )
    (net (code "92") (name "/GPIO3_P") (class "Default")
      (node (ref "P2") (pin "7") (pinfunction "7_7") (pintype "passive"))
      (node (ref "U1") (pin "M9") (pinfunction "IO_L29P_GCLK3_2_M9") (pintype "bidirectional"))
    )
    (net (code "93") (name "/GPIO4_N") (class "Default")
      (node (ref "P2") (pin "10") (pinfunction "10_10") (pintype "passive"))
      (node (ref "U1") (pin "T8") (pinfunction "IO_L30N_GCLK0_USERCCLK_2_T8") (pintype "bidirectional"))
    )
    (net (code "94") (name "/GPIO4_P") (class "Default")
      (node (ref "P2") (pin "9") (pinfunction "9_9") (pintype "passive"))
      (node (ref "U1") (pin "P8") (pinfunction "IO_L30P_GCLK1_D13_2_P8") (pintype "bidirectional"))
    )
    (net (code "95") (name "/GPIO5_N") (class "Default")
      (node (ref "P2") (pin "14") (pinfunction "14_14") (pintype "passive"))
      (node (ref "U1") (pin "M7") (pinfunction "IO_L31N_GCLK30_D15_2_M7") (pintype "bidirectional"))
    )
    (net (code "96") (name "/GPIO5_P") (class "Default")
      (node (ref "P2") (pin "13") (pinfunction "13_13") (pintype "passive"))
      (node (ref "U1") (pin "P7") (pinfunction "IO_L31P_GCLK31_D14_2_P7") (pintype "bidirectional"))
    )
    (net (code "97") (name "/GPIO6_N") (class "Default")
      (node (ref "P2") (pin "16") (pinfunction "16_16") (pintype "passive"))
      (node (ref "U1") (pin "T6") (pinfunction "IO_L47N_2_T6") (pintype "bidirectional"))
    )
    (net (code "98") (name "/GPIO6_P") (class "Default")
      (node (ref "P2") (pin "15") (pinfunction "15_15") (pintype "passive"))
      (node (ref "U1") (pin "P6") (pinfunction "IO_L47P_2_P6") (pintype "bidirectional"))
    )
    (net (code "99") (name "/GPIO7_N") (class "Default")
      (node (ref "P2") (pin "18") (pinfunction "18_18") (pintype "passive"))
      (node (ref "U1") (pin "T5") (pinfunction "IO_L48N_RDWR_B_VREF_2_T5") (pintype "bidirectional"))
    )
    (net (code "100") (name "/GPIO7_P") (class "Default")
      (node (ref "P2") (pin "17") (pinfunction "17_17") (pintype "passive"))
      (node (ref "U1") (pin "R5") (pinfunction "IO_L48P_D7_2_R5") (pintype "bidirectional"))
    )
    (net (code "101") (name "/GPIO8_N") (class "Default")
      (node (ref "P2") (pin "20") (pinfunction "20_20") (pintype "passive"))
      (node (ref "U1") (pin "P5") (pinfunction "IO_L49N_D4_2_P5") (pintype "bidirectional"))
    )
    (net (code "102") (name "/GPIO8_P") (class "Default")
      (node (ref "P2") (pin "19") (pinfunction "19_19") (pintype "passive"))
      (node (ref "U1") (pin "N5") (pinfunction "IO_L49P_D3_2_N5") (pintype "bidirectional"))
    )
    (net (code "103") (name "/GPIO9_N") (class "Default")
      (node (ref "P2") (pin "22") (pinfunction "22_22") (pintype "passive"))
      (node (ref "U1") (pin "L7") (pinfunction "IO_L62N_D6_2_L7") (pintype "bidirectional"))
    )
    (net (code "104") (name "/GPIO9_P") (class "Default")
      (node (ref "P2") (pin "21") (pinfunction "21_21") (pintype "passive"))
      (node (ref "U1") (pin "L8") (pinfunction "IO_L62P_D5_2_L8") (pintype "bidirectional"))
    )
    (net (code "105") (name "/GPIO10_N") (class "Default")
      (node (ref "P2") (pin "24") (pinfunction "24_24") (pintype "passive"))
      (node (ref "U1") (pin "T4") (pinfunction "IO_L63N_2_T4") (pintype "bidirectional"))
    )
    (net (code "106") (name "/GPIO10_P") (class "Default")
      (node (ref "P2") (pin "23") (pinfunction "23_23") (pintype "passive"))
      (node (ref "U1") (pin "P4") (pinfunction "IO_L63P_2_P4") (pintype "bidirectional"))
    )
    (net (code "107") (name "/GPIO11_N") (class "Default")
      (node (ref "P2") (pin "26") (pinfunction "26_26") (pintype "passive"))
      (node (ref "U1") (pin "N6") (pinfunction "IO_L64N_D9_2_N6") (pintype "bidirectional"))
    )
    (net (code "108") (name "/GPIO11_P") (class "Default")
      (node (ref "P2") (pin "25") (pinfunction "25_25") (pintype "passive"))
      (node (ref "U1") (pin "M6") (pinfunction "IO_L64P_D8_2_M6") (pintype "bidirectional"))
    )
    (net (code "109") (name "/GPIO12_N") (class "Default")
      (node (ref "P2") (pin "28") (pinfunction "28_28") (pintype "passive"))
      (node (ref "U1") (pin "K16") (pinfunction "IO_L44N_A2_M1DQ7_1_K16") (pintype "bidirectional"))
    )
    (net (code "110") (name "/GPIO12_P") (class "Default")
      (node (ref "P2") (pin "27") (pinfunction "27_27") (pintype "passive"))
      (node (ref "U1") (pin "K15") (pinfunction "IO_L44P_A3_M1DQ6_1_K15") (pintype "bidirectional"))
    )
    (net (code "111") (name "/GPIO13_N") (class "Default")
      (node (ref "P2") (pin "32") (pinfunction "32_32") (pintype "passive"))
      (node (ref "U1") (pin "N16") (pinfunction "IO_L45N_A0_M1LDQSN_1_N16") (pintype "bidirectional"))
    )
    (net (code "112") (name "/GPIO13_P") (class "Default")
      (node (ref "P2") (pin "31") (pinfunction "31_31") (pintype "passive"))
      (node (ref "U1") (pin "N14") (pinfunction "IO_L45P_A1_M1LDQS_1_N14") (pintype "bidirectional"))
    )
    (net (code "113") (name "/GPIO14_N") (class "Default")
      (node (ref "P2") (pin "34") (pinfunction "34_34") (pintype "passive"))
      (node (ref "U1") (pin "M16") (pinfunction "IO_L46N_FOE_B_M1DQ3_1_M16") (pintype "bidirectional"))
    )
    (net (code "114") (name "/GPIO14_P") (class "Default")
      (node (ref "P2") (pin "33") (pinfunction "33_33") (pintype "passive"))
      (node (ref "U1") (pin "M15") (pinfunction "IO_L46P_FCS_B_M1DQ2_1_M15") (pintype "bidirectional"))
    )
    (net (code "115") (name "/GPIO15_N") (class "Default")
      (node (ref "P2") (pin "36") (pinfunction "36_36") (pintype "passive"))
      (node (ref "U1") (pin "L16") (pinfunction "IO_L47N_LDC_M1DQ1_1_L16") (pintype "bidirectional"))
    )
    (net (code "116") (name "/GPIO15_P") (class "Default")
      (node (ref "P2") (pin "35") (pinfunction "35_35") (pintype "passive"))
      (node (ref "U1") (pin "L14") (pinfunction "IO_L47P_FWE_B_M1DQ0_1_L14") (pintype "bidirectional"))
    )
    (net (code "117") (name "/GPIO_31") (class "Default")
      (node (ref "P2") (pin "37") (pinfunction "37_37") (pintype "passive"))
      (node (ref "U1") (pin "P15") (pinfunction "IO_L48P_HDC_M1DQ8_1_P15") (pintype "bidirectional"))
    )
    (net (code "118") (name "/GPIO_32") (class "Default")
      (node (ref "P2") (pin "38") (pinfunction "38_38") (pintype "passive"))
      (node (ref "U1") (pin "J16") (pinfunction "IO_L43N_GCLK4_M1DQ5_1_J16") (pintype "bidirectional"))
    )
    (net (code "119") (name "/GPIO_33") (class "Default")
      (node (ref "P2") (pin "39") (pinfunction "39_39") (pintype "passive"))
      (node (ref "U1") (pin "P11") (pinfunction "IO_L13N_D10_2_P11") (pintype "bidirectional"))
    )
    (net (code "120") (name "/GPIO_34") (class "Default")
      (node (ref "P2") (pin "40") (pinfunction "40_40") (pintype "passive"))
      (node (ref "U1") (pin "M11") (pinfunction "IO_L2N_CMPMOSI_2_M11") (pintype "bidirectional"))
    )
    (net (code "121") (name "/HDMI_CEC_LV") (class "Default")
      (node (ref "R57") (pin "2") (pinfunction "2_2") (pintype "passive"))
    )
    (net (code "122") (name "/HDMI_CFG_SCL") (class "Default")
      (node (ref "U1") (pin "K12") (pinfunction "IO_L42P_GCLK7_M1UDM_1_K12") (pintype "bidirectional"))
    )
    (net (code "123") (name "/HDMI_CFG_SDA") (class "Default")
      (node (ref "U1") (pin "K14") (pinfunction "IO_L41N_GCLK8_M1CASN_1_K14") (pintype "bidirectional"))
    )
    (net (code "124") (name "/HDMI_D0") (class "Default")
      (node (ref "U1") (pin "H14") (pinfunction "IO_L39N_M1ODT_1_H14") (pintype "bidirectional"))
    )
    (net (code "125") (name "/HDMI_D1") (class "Default")
      (node (ref "U1") (pin "H13") (pinfunction "IO_L39P_M1A3_1_H13") (pintype "bidirectional"))
    )
    (net (code "126") (name "/HDMI_D2") (class "Default")
      (node (ref "U1") (pin "H11") (pinfunction "IO_L38N_A4_M1CLKN_1_H11") (pintype "bidirectional"))
    )
    (net (code "127") (name "/HDMI_D3") (class "Default")
      (node (ref "U1") (pin "G12") (pinfunction "IO_L38P_A5_M1CLK_1_G12") (pintype "bidirectional"))
    )
    (net (code "128") (name "/HDMI_D4") (class "Default")
      (node (ref "U1") (pin "H16") (pinfunction "IO_L37N_A6_M1A1_1_H16") (pintype "bidirectional"))
    )
    (net (code "129") (name "/HDMI_D5") (class "Default")
      (node (ref "U1") (pin "H15") (pinfunction "IO_L37P_A7_M1A0_1_H15") (pintype "bidirectional"))
    )
    (net (code "130") (name "/HDMI_D6") (class "Default")
      (node (ref "U1") (pin "G16") (pinfunction "IO_L36N_A8_M1BA1_1_G16") (pintype "bidirectional"))
    )
    (net (code "131") (name "/HDMI_D7") (class "Default")
      (node (ref "U1") (pin "G14") (pinfunction "IO_L36P_A9_M1BA0_1_G14") (pintype "bidirectional"))
    )
    (net (code "132") (name "/HDMI_D8") (class "Default")
      (node (ref "U1") (pin "F16") (pinfunction "IO_L35N_A10_M1A2_1_F16") (pintype "bidirectional"))
    )
    (net (code "133") (name "/HDMI_D9") (class "Default")
      (node (ref "U1") (pin "F15") (pinfunction "IO_L35P_A11_M1A7_1_F15") (pintype "bidirectional"))
    )
    (net (code "134") (name "/HDMI_D10") (class "Default")
      (node (ref "U1") (pin "E16") (pinfunction "IO_L34N_A12_M1BA2_1_E16") (pintype "bidirectional"))
    )
    (net (code "135") (name "/HDMI_D11") (class "Default")
      (node (ref "U1") (pin "E15") (pinfunction "IO_L34P_A13_M1WE_1_E15") (pintype "bidirectional"))
    )
    (net (code "136") (name "/HDMI_D12") (class "Default")
      (node (ref "U1") (pin "C16") (pinfunction "IO_L33N_A14_M1A4_1_C16") (pintype "bidirectional"))
    )
    (net (code "137") (name "/HDMI_D13") (class "Default")
      (node (ref "U1") (pin "C15") (pinfunction "IO_L33P_A15_M1A10_1_C15") (pintype "bidirectional"))
    )
    (net (code "138") (name "/HDMI_D14") (class "Default")
      (node (ref "U1") (pin "F14") (pinfunction "IO_L32N_A16_M1A9_1_F14") (pintype "bidirectional"))
    )
    (net (code "139") (name "/HDMI_D15") (class "Default")
      (node (ref "U1") (pin "F13") (pinfunction "IO_L32P_A17_M1A8_1_F13") (pintype "bidirectional"))
    )
    (net (code "140") (name "/HDMI_D16") (class "Default")
      (node (ref "U1") (pin "D16") (pinfunction "IO_L31N_A18_M1A12_1_D16") (pintype "bidirectional"))
    )
    (net (code "141") (name "/HDMI_D17") (class "Default")
      (node (ref "U1") (pin "D14") (pinfunction "IO_L31P_A19_M1CKE_1_D14") (pintype "bidirectional"))
    )
    (net (code "142") (name "/HDMI_D18") (class "Default")
      (node (ref "U1") (pin "G11") (pinfunction "IO_L30N_A20_M1A11_1_G11") (pintype "bidirectional"))
    )
    (net (code "143") (name "/HDMI_D19") (class "Default")
      (node (ref "U1") (pin "F12") (pinfunction "IO_L30P_A21_M1RESET_1_F12") (pintype "bidirectional"))
    )
    (net (code "144") (name "/HDMI_D20") (class "Default")
      (node (ref "U1") (pin "B16") (pinfunction "IO_L29N_A22_M1A14_1_B16") (pintype "bidirectional"))
    )
    (net (code "145") (name "/HDMI_D21") (class "Default")
      (node (ref "U1") (pin "B15") (pinfunction "IO_L29P_A23_M1A13_1_B15") (pintype "bidirectional"))
    )
    (net (code "146") (name "/HDMI_D22") (class "Default")
      (node (ref "U1") (pin "E12") (pinfunction "IO_L1N_A24_VREF_1_E12") (pintype "bidirectional"))
    )
    (net (code "147") (name "/HDMI_D23") (class "Default")
      (node (ref "U1") (pin "E13") (pinfunction "IO_L1P_A25_1_E13") (pintype "bidirectional"))
    )
    (net (code "148") (name "/HDMI_DE") (class "Default")
      (node (ref "U1") (pin "J13") (pinfunction "IO_L41P_GCLK9_IRDY1_M1RASN_1_J13") (pintype "bidirectional"))
    )
    (net (code "150") (name "/HDMI_HS") (class "Default")
      (node (ref "U1") (pin "J12") (pinfunction "IO_L40N_GCLK10_M1A6_1_J12") (pintype "bidirectional"))
    )
    (net (code "151") (name "/HDMI_LCC") (class "Default")
      (node (ref "U1") (pin "J14") (pinfunction "IO_L43P_GCLK5_M1DQ4_1_J14") (pintype "bidirectional"))
    )
    (net (code "152") (name "/HDMI_RST_N") (class "Default")
      (node (ref "U1") (pin "K11") (pinfunction "IO_L42N_GCLK6_TRDY1_M1LDM_1_K11") (pintype "bidirectional"))
    )
    (net (code "153") (name "/HDMI_SCL_LV") (class "Default")
      (node (ref "U1") (pin "R15") (pinfunction "IO_L49P_M1DQ10_1_R15") (pintype "bidirectional"))
    )
    (net (code "154") (name "/HDMI_SDA_LV") (class "Default")
      (node (ref "U1") (pin "P16") (pinfunction "IO_L48N_M1DQ9_1_P16") (pintype "bidirectional"))
    )
    (net (code "155") (name "/HDMI_VS") (class "Default")
      (node (ref "U1") (pin "J11") (pinfunction "IO_L40P_GCLK11_M1A5_1_J11") (pintype "bidirectional"))
    )
    (net (code "156") (name "/HDP_EN") (class "Default")
      (node (ref "U1") (pin "R14") (pinfunction "IO_L50P_M1UDQS_1_R14") (pintype "bidirectional"))
    )
    (net (code "157") (name "/HPD_NOTIF") (class "Default")
      (node (ref "U1") (pin "T15") (pinfunction "IO_L50N_M1UDQSN_1_T15") (pintype "bidirectional"))
    )
    (net (code "158") (name "/LCD_BL_EN") (class "Default")
      (node (ref "U1") (pin "B5") (pinfunction "IO_L2P_0_B5") (pintype "bidirectional"))
    )
    (net (code "159") (name "/LCD_PWREN") (class "Default")
      (node (ref "U1") (pin "D8") (pinfunction "IO_L38P_0_D8") (pintype "bidirectional"))
    )
    (net (code "160") (name "/RST_CPU") (class "Default")
      (node (ref "R39") (pin "2") (pinfunction "2_2") (pintype "passive"))
    )
    (net (code "161") (name "/SYS_CLK") (class "Default")
      (node (ref "OSC1") (pin "3") (pinfunction "OUT_3") (pintype "output"))
      (node (ref "R32") (pin "2") (pinfunction "2_2") (pintype "passive"))
    )
    (net (code "162") (name "/TCK") (class "Default")
      (node (ref "P1") (pin "6") (pinfunction "6_6") (pintype "passive"))
      (node (ref "R37") (pin "1") (pinfunction "1_1") (pintype "passive"))
      (node (ref "U1") (pin "C14") (pinfunction "TCK_C14") (pintype "input"))
    )
    (net (code "163") (name "/TDI") (class "Default")
      (node (ref "P1") (pin "5") (pinfunction "5_5") (pintype "passive"))
      (node (ref "U1") (pin "C12") (pinfunction "TDI_C12") (pintype "input"))
    )
    (net (code "164") (name "/TDO") (class "Default")
      (node (ref "P1") (pin "4") (pinfunction "4_4") (pintype "passive"))
      (node (ref "U1") (pin "E14") (pinfunction "TDO_E14") (pintype "output"))
    )
    (net (code "165") (name "/TMDS0_N") (class "Default")
      (node (ref "R69") (pin "1") (pinfunction "1_1") (pintype "passive"))
      (node (ref "U1") (pin "T13") (pinfunction "IO_L51N_M1DQ13_1_T13") (pintype "bidirectional"))
    )
    (net (code "166") (name "/TMDS0_P") (class "Default")
      (node (ref "R71") (pin "1") (pinfunction "1_1") (pintype "passive"))
      (node (ref "U1") (pin "T14") (pinfunction "IO_L51P_M1DQ12_1_T14") (pintype "bidirectional"))
    )
    (net (code "167") (name "/TMDS1_N") (class "Default")
      (node (ref "R67") (pin "1") (pinfunction "1_1") (pintype "passive"))
      (node (ref "U1") (pin "T12") (pinfunction "IO_L52N_M1DQ15_1_T12") (pintype "bidirectional"))
    )
    (net (code "168") (name "/TMDS1_P") (class "Default")
      (node (ref "R68") (pin "1") (pinfunction "1_1") (pintype "passive"))
      (node (ref "U1") (pin "R12") (pinfunction "IO_L52P_M1DQ14_1_R12") (pintype "bidirectional"))
    )
    (net (code "169") (name "/TMDS2_N") (class "Default")
      (node (ref "R73") (pin "2") (pinfunction "2_2") (pintype "passive"))
      (node (ref "U1") (pin "L13") (pinfunction "IO_L53N_VREF_1_L13") (pintype "bidirectional"))
    )
    (net (code "170") (name "/TMDS2_P") (class "Default")
      (node (ref "R72") (pin "2") (pinfunction "2_2") (pintype "passive"))
      (node (ref "U1") (pin "L12") (pinfunction "IO_L53P_1_L12") (pintype "bidirectional"))
    )
    (net (code "171") (name "/TMDS_CLK_N") (class "Default")
      (node (ref "R89") (pin "2") (pinfunction "2_2") (pintype "passive"))
      (node (ref "U1") (pin "M14") (pinfunction "IO_L74N_DOUT_BUSY_1_M14") (pintype "bidirectional"))
    )
    (net (code "172") (name "/TMDS_CLK_P") (class "Default")
      (node (ref "R88") (pin "2") (pinfunction "2_2") (pintype "passive"))
      (node (ref "U1") (pin "M13") (pinfunction "IO_L74P_AWAKE_1_M13") (pintype "bidirectional"))
    )
    (net (code "173") (name "/TMS") (class "Default")
      (node (ref "P1") (pin "3") (pinfunction "3_3") (pintype "passive"))
      (node (ref "U1") (pin "A15") (pinfunction "TMS_A15") (pintype "input"))
    )
    (net (code "174") (name "/UART_RX") (class "Default")
      (node (ref "U1") (pin "N12") (pinfunction "IO_L12P_D1_MISO2_2_N12") (pintype "bidirectional"))
    )
    (net (code "175") (name "/UART_TX") (class "Default")
      (node (ref "U1") (pin "P12") (pinfunction "IO_L12N_D2_MISO3_2_P12") (pintype "bidirectional"))
    )
    (net (code "176") (name "/USER_LED") (class "Default")
      (node (ref "LD2") (pin "2") (pinfunction "A_2") (pintype "passive"))
      (node (ref "U1") (pin "R7") (pinfunction "IO_L32P_GCLK29_2_R7") (pintype "bidirectional"))
    )
    (net (code "177") (name "1V2") (class "Default")
      (node (ref "C49") (pin "2") (pinfunction "2_2") (pintype "passive"))
      (node (ref "C51") (pin "2") (pinfunction "2_2") (pintype "passive"))
      (node (ref "C52") (pin "2") (pinfunction "2_2") (pintype "passive"))
      (node (ref "C9") (pin "2") (pinfunction "2_2") (pintype "passive"))
      (node (ref "U1") (pin "G7") (pinfunction "VCCINT_G7") (pintype "power_in"))
      (node (ref "U1") (pin "G9") (pinfunction "VCCINT_G9") (pintype "power_in"))
      (node (ref "U1") (pin "H10") (pinfunction "VCCINT_H10") (pintype "power_in"))
      (node (ref "U1") (pin "H8") (pinfunction "VCCINT_H8") (pintype "power_in"))
      (node (ref "U1") (pin "J7") (pinfunction "VCCINT_J7") (pintype "power_in"))
      (node (ref "U1") (pin "J9") (pinfunction "VCCINT_J9") (pintype "power_in"))
      (node (ref "U1") (pin "K10") (pinfunction "VCCINT_K10") (pintype "power_in"))
      (node (ref "U1") (pin "K8") (pinfunction "VCCINT_K8") (pintype "power_in"))
    )
    (net (code "178") (name "1V5") (class "Default")
      (node (ref "C13") (pin "2") (pinfunction "2_2") (pintype "passive"))
      (node (ref "C56") (pin "2") (pinfunction "2_2") (pintype "passive"))
      (node (ref "C58") (pin "2") (pinfunction "2_2") (pintype "passive"))
      (node (ref "U1") (pin "D2") (pinfunction "VCCO_3_D2") (pintype "power_in"))
      (node (ref "U1") (pin "G4") (pinfunction "VCCO_3_G4") (pintype "power_in"))
      (node (ref "U1") (pin "J2") (pinfunction "VCCO_3_J2") (pintype "power_in"))
      (node (ref "U1") (pin "K4") (pinfunction "VCCO_3_K4") (pintype "power_in"))
      (node (ref "U1") (pin "N2") (pinfunction "VCCO_3_N2") (pintype "power_in"))
    )
    (net (code "179") (name "1V8") (class "Default")
      (node (ref "C3") (pin "2") (pinfunction "2_2") (pintype "passive"))
      (node (ref "C38") (pin "2") (pinfunction "2_2") (pintype "passive"))
      (node (ref "C41") (pin "2") (pinfunction "2_2") (pintype "passive"))
      (node (ref "R47") (pin "2") (pinfunction "2_2") (pintype "passive"))
      (node (ref "R48") (pin "2") (pinfunction "2_2") (pintype "passive"))
      (node (ref "R76") (pin "2") (pinfunction "2_2") (pintype "passive"))
      (node (ref "U1") (pin "B13") (pinfunction "VCCO_0_B13") (pintype "power_in"))
      (node (ref "U1") (pin "B4") (pinfunction "VCCO_0_B4") (pintype "power_in"))
      (node (ref "U1") (pin "B9") (pinfunction "VCCO_0_B9") (pintype "power_in"))
      (node (ref "U1") (pin "D10") (pinfunction "VCCO_0_D10") (pintype "power_in"))
      (node (ref "U1") (pin "D7") (pinfunction "VCCO_0_D7") (pintype "power_in"))
      (node (ref "U8") (pin "4") (pinfunction "VCC_4") (pintype "power_in"))
    )
    (net (code "180") (name "3V3") (class "Default")
      (node (ref "C12") (pin "2") (pinfunction "2_2") (pintype "passive"))
      (node (ref "C2") (pin "2") (pinfunction "2_2") (pintype "passive"))
      (node (ref "C42") (pin "2") (pinfunction "2_2") (pintype "passive"))
      (node (ref "C44") (pin "2") (pinfunction "2_2") (pintype "passive"))
      (node (ref "C45") (pin "2") (pinfunction "2_2") (pintype "passive"))
      (node (ref "C46") (pin "2") (pinfunction "2_2") (pintype "passive"))
      (node (ref "C48") (pin "2") (pinfunction "2_2") (pintype "passive"))
      (node (ref "C5") (pin "2") (pinfunction "2_2") (pintype "passive"))
      (node (ref "C53") (pin "2") (pinfunction "2_2") (pintype "passive"))
      (node (ref "C55") (pin "2") (pinfunction "2_2") (pintype "passive"))
      (node (ref "C60") (pin "2") (pinfunction "2_2") (pintype "passive"))
      (node (ref "C8") (pin "2") (pinfunction "2_2") (pintype "passive"))
      (node (ref "OSC1") (pin "4") (pinfunction "+Vs_4") (pintype "power_in"))
      (node (ref "P1") (pin "2") (pinfunction "2_2") (pintype "passive"))
      (node (ref "P2") (pin "29") (pinfunction "29_29") (pintype "passive"))
      (node (ref "R34") (pin "1") (pinfunction "1_1") (pintype "passive"))
      (node (ref "R35") (pin "2") (pinfunction "2_2") (pintype "passive"))
      (node (ref "R36") (pin "1") (pinfunction "1_1") (pintype "passive"))
      (node (ref "R37") (pin "2") (pinfunction "2_2") (pintype "passive"))
      (node (ref "R38") (pin "2") (pinfunction "2_2") (pintype "passive"))
      (node (ref "R40") (pin "2") (pinfunction "2_2") (pintype "passive"))
      (node (ref "R41") (pin "2") (pinfunction "2_2") (pintype "passive"))
      (node (ref "R43") (pin "2") (pinfunction "2_2") (pintype "passive"))
      (node (ref "R45") (pin "2") (pinfunction "2_2") (pintype "passive"))
      (node (ref "R46") (pin "2") (pinfunction "2_2") (pintype "passive"))
      (node (ref "R67") (pin "2") (pinfunction "2_2") (pintype "passive"))
      (node (ref "R68") (pin "2") (pinfunction "2_2") (pintype "passive"))
      (node (ref "R69") (pin "2") (pinfunction "2_2") (pintype "passive"))
      (node (ref "R71") (pin "2") (pinfunction "2_2") (pintype "passive"))
      (node (ref "R72") (pin "1") (pinfunction "1_1") (pintype "passive"))
      (node (ref "R73") (pin "1") (pinfunction "1_1") (pintype "passive"))
      (node (ref "R88") (pin "1") (pinfunction "1_1") (pintype "passive"))
      (node (ref "R89") (pin "1") (pinfunction "1_1") (pintype "passive"))
      (node (ref "U1") (pin "D15") (pinfunction "VCCO_1_D15") (pintype "power_in"))
      (node (ref "U1") (pin "E5") (pinfunction "VCCAUX_E5") (pintype "power_in"))
      (node (ref "U1") (pin "F11") (pinfunction "VCCAUX_F11") (pintype "power_in"))
      (node (ref "U1") (pin "F8") (pinfunction "VCCAUX_F8") (pintype "power_in"))
      (node (ref "U1") (pin "G10") (pinfunction "VCCAUX_G10") (pintype "power_in"))
      (node (ref "U1") (pin "G13") (pinfunction "VCCO_1_G13") (pintype "power_in"))
      (node (ref "U1") (pin "H6") (pinfunction "VCCAUX_H6") (pintype "power_in"))
      (node (ref "U1") (pin "J10") (pinfunction "VCCAUX_J10") (pintype "power_in"))
      (node (ref "U1") (pin "J15") (pinfunction "VCCO_1_J15") (pintype "power_in"))
      (node (ref "U1") (pin "K13") (pinfunction "VCCO_1_K13") (pintype "power_in"))
      (node (ref "U1") (pin "L6") (pinfunction "VCCAUX_L6") (pintype "power_in"))
      (node (ref "U1") (pin "L9") (pinfunction "VCCAUX_L9") (pintype "power_in"))
      (node (ref "U1") (pin "N10") (pinfunction "VCCO_2_N10") (pintype "power_in"))
      (node (ref "U1") (pin "N15") (pinfunction "VCCO_1_N15") (pintype "power_in"))
      (node (ref "U1") (pin "N7") (pinfunction "VCCO_2_N7") (pintype "power_in"))
      (node (ref "U1") (pin "R13") (pinfunction "VCCO_1_R13") (pintype "power_in"))
      (node (ref "U1") (pin "R4") (pinfunction "VCCO_2_R4") (pintype "power_in"))
      (node (ref "U1") (pin "R8") (pinfunction "VCCO_2_R8") (pintype "power_in"))
      (node (ref "U2") (pin "8") (pinfunction "VCC_8") (pintype "power_in"))
    )
    (net (code "181") (name "5V_IN") (class "Default")
      (node (ref "P2") (pin "11") (pinfunction "11_11") (pintype "passive"))
    )
    (net (code "182") (name "DDR_VREF") (class "Default")
      (node (ref "C1") (pin "2") (pinfunction "2_2") (pintype "passive"))
      (node (ref "C30") (pin "1") (pinfunction "1_1") (pintype "passive"))
      (node (ref "U1") (pin "A3") (pinfunction "IO_L83N_VREF_3_A3") (pintype "bidirectional"))
      (node (ref "U1") (pin "M3") (pinfunction "IO_L1N_VREF_3_M3") (pintype "bidirectional"))
    )
    (net (code "183") (name "GND") (class "Default")
      (node (ref "C1") (pin "1") (pinfunction "1_1") (pintype "passive"))
      (node (ref "C12") (pin "1") (pinfunction "1_1") (pintype "passive"))
      (node (ref "C13") (pin "1") (pinfunction "1_1") (pintype "passive"))
      (node (ref "C2") (pin "1") (pinfunction "1_1") (pintype "passive"))
      (node (ref "C3") (pin "1") (pinfunction "1_1") (pintype "passive"))
      (node (ref "C30") (pin "2") (pinfunction "2_2") (pintype "passive"))
      (node (ref "C38") (pin "1") (pinfunction "1_1") (pintype "passive"))
      (node (ref "C41") (pin "1") (pinfunction "1_1") (pintype "passive"))
      (node (ref "C42") (pin "1") (pinfunction "1_1") (pintype "passive"))
      (node (ref "C44") (pin "1") (pinfunction "1_1") (pintype "passive"))
      (node (ref "C45") (pin "1") (pinfunction "1_1") (pintype "passive"))
      (node (ref "C46") (pin "1") (pinfunction "1_1") (pintype "passive"))
      (node (ref "C48") (pin "1") (pinfunction "1_1") (pintype "passive"))
      (node (ref "C49") (pin "1") (pinfunction "1_1") (pintype "passive"))
      (node (ref "C5") (pin "1") (pinfunction "1_1") (pintype "passive"))
      (node (ref "C51") (pin "1") (pinfunction "1_1") (pintype "passive"))
      (node (ref "C52") (pin "1") (pinfunction "1_1") (pintype "passive"))
      (node (ref "C53") (pin "1") (pinfunction "1_1") (pintype "passive"))
      (node (ref "C55") (pin "1") (pinfunction "1_1") (pintype "passive"))
      (node (ref "C56") (pin "1") (pinfunction "1_1") (pintype "passive"))
      (node (ref "C58") (pin "1") (pinfunction "1_1") (pintype "passive"))
      (node (ref "C60") (pin "1") (pinfunction "1_1") (pintype "passive"))
      (node (ref "C8") (pin "1") (pinfunction "1_1") (pintype "passive"))
      (node (ref "C80") (pin "2") (pinfunction "2_2") (pintype "passive"))
      (node (ref "C9") (pin "1") (pinfunction "1_1") (pintype "passive"))
      (node (ref "OSC1") (pin "2") (pinfunction "GND_2") (pintype "power_in"))
      (node (ref "P1") (pin "1") (pinfunction "1_1") (pintype "passive"))
      (node (ref "P2") (pin "12") (pinfunction "12_12") (pintype "passive"))
      (node (ref "P2") (pin "30") (pinfunction "30_30") (pintype "passive"))
      (node (ref "PB1") (pin "3") (pinfunction "3_3") (pintype "passive"))
      (node (ref "PB1") (pin "4") (pinfunction "4_4") (pintype "passive"))
      (node (ref "R13") (pin "2") (pinfunction "2_2") (pintype "passive"))
      (node (ref "R33") (pin "1") (pinfunction "1_1") (pintype "passive"))
      (node (ref "R42") (pin "1") (pinfunction "1_1") (pintype "passive"))
      (node (ref "R44") (pin "1") (pinfunction "1_1") (pintype "passive"))
      (node (ref "R49") (pin "2") (pinfunction "2_2") (pintype "passive"))
      (node (ref "R66") (pin "2") (pinfunction "2_2") (pintype "passive"))
      (node (ref "R75") (pin "1") (pinfunction "1_1") (pintype "passive"))
      (node (ref "U1") (pin "A1") (pinfunction "GND_A1") (pintype "power_in"))
      (node (ref "U1") (pin "A16") (pinfunction "GND_A16") (pintype "power_in"))
      (node (ref "U1") (pin "B11") (pinfunction "GND_B11") (pintype "power_in"))
      (node (ref "U1") (pin "B7") (pinfunction "GND_B7") (pintype "power_in"))
      (node (ref "U1") (pin "D13") (pinfunction "GND_D13") (pintype "power_in"))
      (node (ref "U1") (pin "D4") (pinfunction "GND_D4") (pintype "power_in"))
      (node (ref "U1") (pin "E9") (pinfunction "GND_E9") (pintype "power_in"))
      (node (ref "U1") (pin "G15") (pinfunction "GND_G15") (pintype "power_in"))
      (node (ref "U1") (pin "G2") (pinfunction "GND_G2") (pintype "power_in"))
      (node (ref "U1") (pin "G8") (pinfunction "GND_G8") (pintype "power_in"))
      (node (ref "U1") (pin "H12") (pinfunction "GND_H12") (pintype "power_in"))
      (node (ref "U1") (pin "H7") (pinfunction "GND_H7") (pintype "power_in"))
      (node (ref "U1") (pin "H9") (pinfunction "GND_H9") (pintype "power_in"))
      (node (ref "U1") (pin "J5") (pinfunction "GND_J5") (pintype "power_in"))
      (node (ref "U1") (pin "J8") (pinfunction "GND_J8") (pintype "power_in"))
      (node (ref "U1") (pin "K7") (pinfunction "GND_K7") (pintype "power_in"))
      (node (ref "U1") (pin "K9") (pinfunction "GND_K9") (pintype "power_in"))
      (node (ref "U1") (pin "L15") (pinfunction "GND_L15") (pintype "power_in"))
      (node (ref "U1") (pin "L2") (pinfunction "GND_L2") (pintype "power_in"))
      (node (ref "U1") (pin "M8") (pinfunction "GND_M8") (pintype "power_in"))
      (node (ref "U1") (pin "N11") (pinfunction "IO_L13P_M1_2_N11") (pintype "bidirectional"))
      (node (ref "U1") (pin "N13") (pinfunction "GND_N13") (pintype "power_in"))
      (node (ref "U1") (pin "P14") (pinfunction "SUSPEND_P14") (pintype "input"))
      (node (ref "U1") (pin "P3") (pinfunction "GND_P3") (pintype "power_in"))
      (node (ref "U1") (pin "R10") (pinfunction "GND_R10") (pintype "power_in"))
      (node (ref "U1") (pin "R6") (pinfunction "GND_R6") (pintype "power_in"))
      (node (ref "U1") (pin "T1") (pinfunction "GND_T1") (pintype "power_in"))
      (node (ref "U1") (pin "T16") (pinfunction "GND_T16") (pintype "power_in"))
      (node (ref "U2") (pin "4") (pinfunction "VSS_4") (pintype "power_in"))
      (node (ref "U8") (pin "2") (pinfunction "VSS_2") (pintype "power_in"))
    )
    (net (code "184") (name "Net-(LD1-C)") (class "Default")
      (node (ref "LD1") (pin "1") (pinfunction "C_1") (pintype "passive"))
      (node (ref "R42") (pin "2") (pinfunction "2_2") (pintype "passive"))
    )
    (net (code "185") (name "Net-(LD2-C)") (class "Default")
      (node (ref "LD2") (pin "1") (pinfunction "C_1") (pintype "passive"))
      (node (ref "R75") (pin "2") (pinfunction "2_2") (pintype "passive"))
    )
    (net (code "186") (name "Net-(OSC1-E)") (class "Default")
      (node (ref "OSC1") (pin "1") (pinfunction "E_1") (pintype "input"))
      (node (ref "R35") (pin "1") (pinfunction "1_1") (pintype "passive"))
    )
    (net (code "187") (name "Net-(U1A-IO_L1P_HSWAPEN_0)") (class "Default")
      (node (ref "R49") (pin "1") (pinfunction "1_1") (pintype "passive"))
      (node (ref "U1") (pin "C4") (pinfunction "IO_L1P_HSWAPEN_0_C4") (pintype "bidirectional"))
    )
    (net (code "188") (name "Net-(U1A-IO_L65N_SCP2_0)") (class "Default")
      (node (ref "C80") (pin "1") (pinfunction "1_1") (pintype "passive"))
      (node (ref "PB1") (pin "1") (pinfunction "1_1") (pintype "passive"))
      (node (ref "PB1") (pin "2") (pinfunction "2_2") (pintype "passive"))
      (node (ref "R76") (pin "1") (pinfunction "1_1") (pintype "passive"))
      (node (ref "U1") (pin "A14") (pinfunction "IO_L65N_SCP2_0_A14") (pintype "bidirectional"))
    )
    (net (code "189") (name "Net-(U1B-IO_L49N_M1DQ11_1)") (class "Default")
      (node (ref "R57") (pin "1") (pinfunction "1_1") (pintype "passive"))
      (node (ref "U1") (pin "R16") (pinfunction "IO_L49N_M1DQ11_1_R16") (pintype "bidirectional"))
    )
    (net (code "190") (name "Net-(U1C-IO_L1N_M0_CMPMISO_2)") (class "Default")
      (node (ref "R45") (pin "1") (pinfunction "1_1") (pintype "passive"))
      (node (ref "U1") (pin "T11") (pinfunction "IO_L1N_M0_CMPMISO_2_T11") (pintype "bidirectional"))
    )
    (net (code "191") (name "Net-(U1C-IO_L32N_GCLK28_2)") (class "Default")
      (node (ref "R32") (pin "1") (pinfunction "1_1") (pintype "passive"))
      (node (ref "R33") (pin "2") (pinfunction "2_2") (pintype "passive"))
      (node (ref "U1") (pin "T7") (pinfunction "IO_L32N_GCLK28_2_T7") (pintype "bidirectional"))
    )
    (net (code "192") (name "Net-(U1C-IO_L65P_INIT_B_2)") (class "Default")
      (node (ref "R46") (pin "1") (pinfunction "1_1") (pintype "passive"))
      (node (ref "U1") (pin "R3") (pinfunction "IO_L65P_INIT_B_2_R3") (pintype "bidirectional"))
    )
    (net (code "193") (name "Net-(U1D-IO_L1P_3)") (class "Default")
      (node (ref "R13") (pin "1") (pinfunction "1_1") (pintype "passive"))
      (node (ref "U1") (pin "M4") (pinfunction "IO_L1P_3_M4") (pintype "bidirectional"))
    )
    (net (code "194") (name "Net-(U1D-IO_L83P_3)") (class "Default")
      (node (ref "R66") (pin "1") (pinfunction "1_1") (pintype "passive"))
      (node (ref "U1") (pin "B3") (pinfunction "IO_L83P_3_B3") (pintype "bidirectional"))
    )
    (net (code "195") (name "Net-(U1E-CMPCS_B_2)") (class "Default")
      (node (ref "R36") (pin "2") (pinfunction "2_2") (pintype "passive"))
      (node (ref "U1") (pin "L11") (pinfunction "CMPCS_B_2_L11") (pintype "input"))
    )
    (net (code "196") (name "Net-(U1E-PROGRAM_B_2)") (class "Default")
      (node (ref "R34") (pin "2") (pinfunction "2_2") (pintype "passive"))
      (node (ref "U1") (pin "T2") (pinfunction "PROGRAM_B_2_T2") (pintype "input"))
    )
    (net (code "197") (name "Net-(U2-HOLD#)") (class "Default")
      (node (ref "R43") (pin "1") (pinfunction "1_1") (pintype "passive"))
      (node (ref "U2") (pin "3") (pinfunction "W#_3") (pintype "input"))
      (node (ref "U2") (pin "7") (pinfunction "HOLD#_7") (pintype "input"))
    )
    (net (code "198") (name "unconnected-(U1A-IO_L1N_VREF_0-PadA4)") (class "Default")
      (node (ref "U1") (pin "A4") (pinfunction "IO_L1N_VREF_0_A4") (pintype "bidirectional"))
    )
    (net (code "199") (name "unconnected-(U1A-IO_L40N_0-PadD9)") (class "Default")
      (node (ref "U1") (pin "D9") (pinfunction "IO_L40N_0_D9") (pintype "bidirectional"))
    )
    (net (code "200") (name "unconnected-(U1A-IO_L62N_VREF_0-PadA12)") (class "Default")
      (node (ref "U1") (pin "A12") (pinfunction "IO_L62N_VREF_0_A12") (pintype "bidirectional"))
    )
    (net (code "201") (name "unconnected-(U1A-IO_L62P_0-PadB12)") (class "Default")
      (node (ref "U1") (pin "B12") (pinfunction "IO_L62P_0_B12") (pintype "bidirectional"))
    )
    (net (code "202") (name "unconnected-(U1A-IO_L63N_SCP6_0-PadA13)") (class "Default")
      (node (ref "U1") (pin "A13") (pinfunction "IO_L63N_SCP6_0_A13") (pintype "bidirectional"))
    )
    (net (code "203") (name "unconnected-(U1A-IO_L63P_SCP7_0-PadC13)") (class "Default")
      (node (ref "U1") (pin "C13") (pinfunction "IO_L63P_SCP7_0_C13") (pintype "bidirectional"))
    )
    (net (code "204") (name "unconnected-(U1A-IO_L64N_SCP4_0-PadE11)") (class "Default")
      (node (ref "U1") (pin "E11") (pinfunction "IO_L64N_SCP4_0_E11") (pintype "bidirectional"))
    )
    (net (code "205") (name "unconnected-(U1A-IO_L64P_SCP5_0-PadF10)") (class "Default")
      (node (ref "U1") (pin "F10") (pinfunction "IO_L64P_SCP5_0_F10") (pintype "bidirectional"))
    )
    (net (code "206") (name "unconnected-(U1A-IO_L65P_SCP3_0-PadB14)") (class "Default")
      (node (ref "U1") (pin "B14") (pinfunction "IO_L65P_SCP3_0_B14") (pintype "bidirectional"))
    )
    (net (code "207") (name "unconnected-(U1C-IO_L2P_CMPCLK_2-PadM12)") (class "Default")
      (node (ref "U1") (pin "M12") (pinfunction "IO_L2P_CMPCLK_2_M12") (pintype "bidirectional"))
    )
    (net (code "208") (name "unconnected-(U1D-IO_L2N_3-PadN4)") (class "Default")
      (node (ref "U1") (pin "N4") (pinfunction "IO_L2N_3_N4") (pintype "bidirectional"))
    )
    (net (code "209") (name "unconnected-(U1D-IO_L2P_3-PadM5)") (class "Default")
      (node (ref "U1") (pin "M5") (pinfunction "IO_L2P_3_M5") (pintype "bidirectional"))
    )
    (net (code "210") (name "unconnected-(U8-WP-Pad5)") (class "Default")
      (node (ref "U8") (pin "5") (pinfunction "WP_5") (pintype "input+no_connect"))
    )
  )
)
